# 05_Codec.net
KiCad netlist of a schematic drawn in Altium Designer
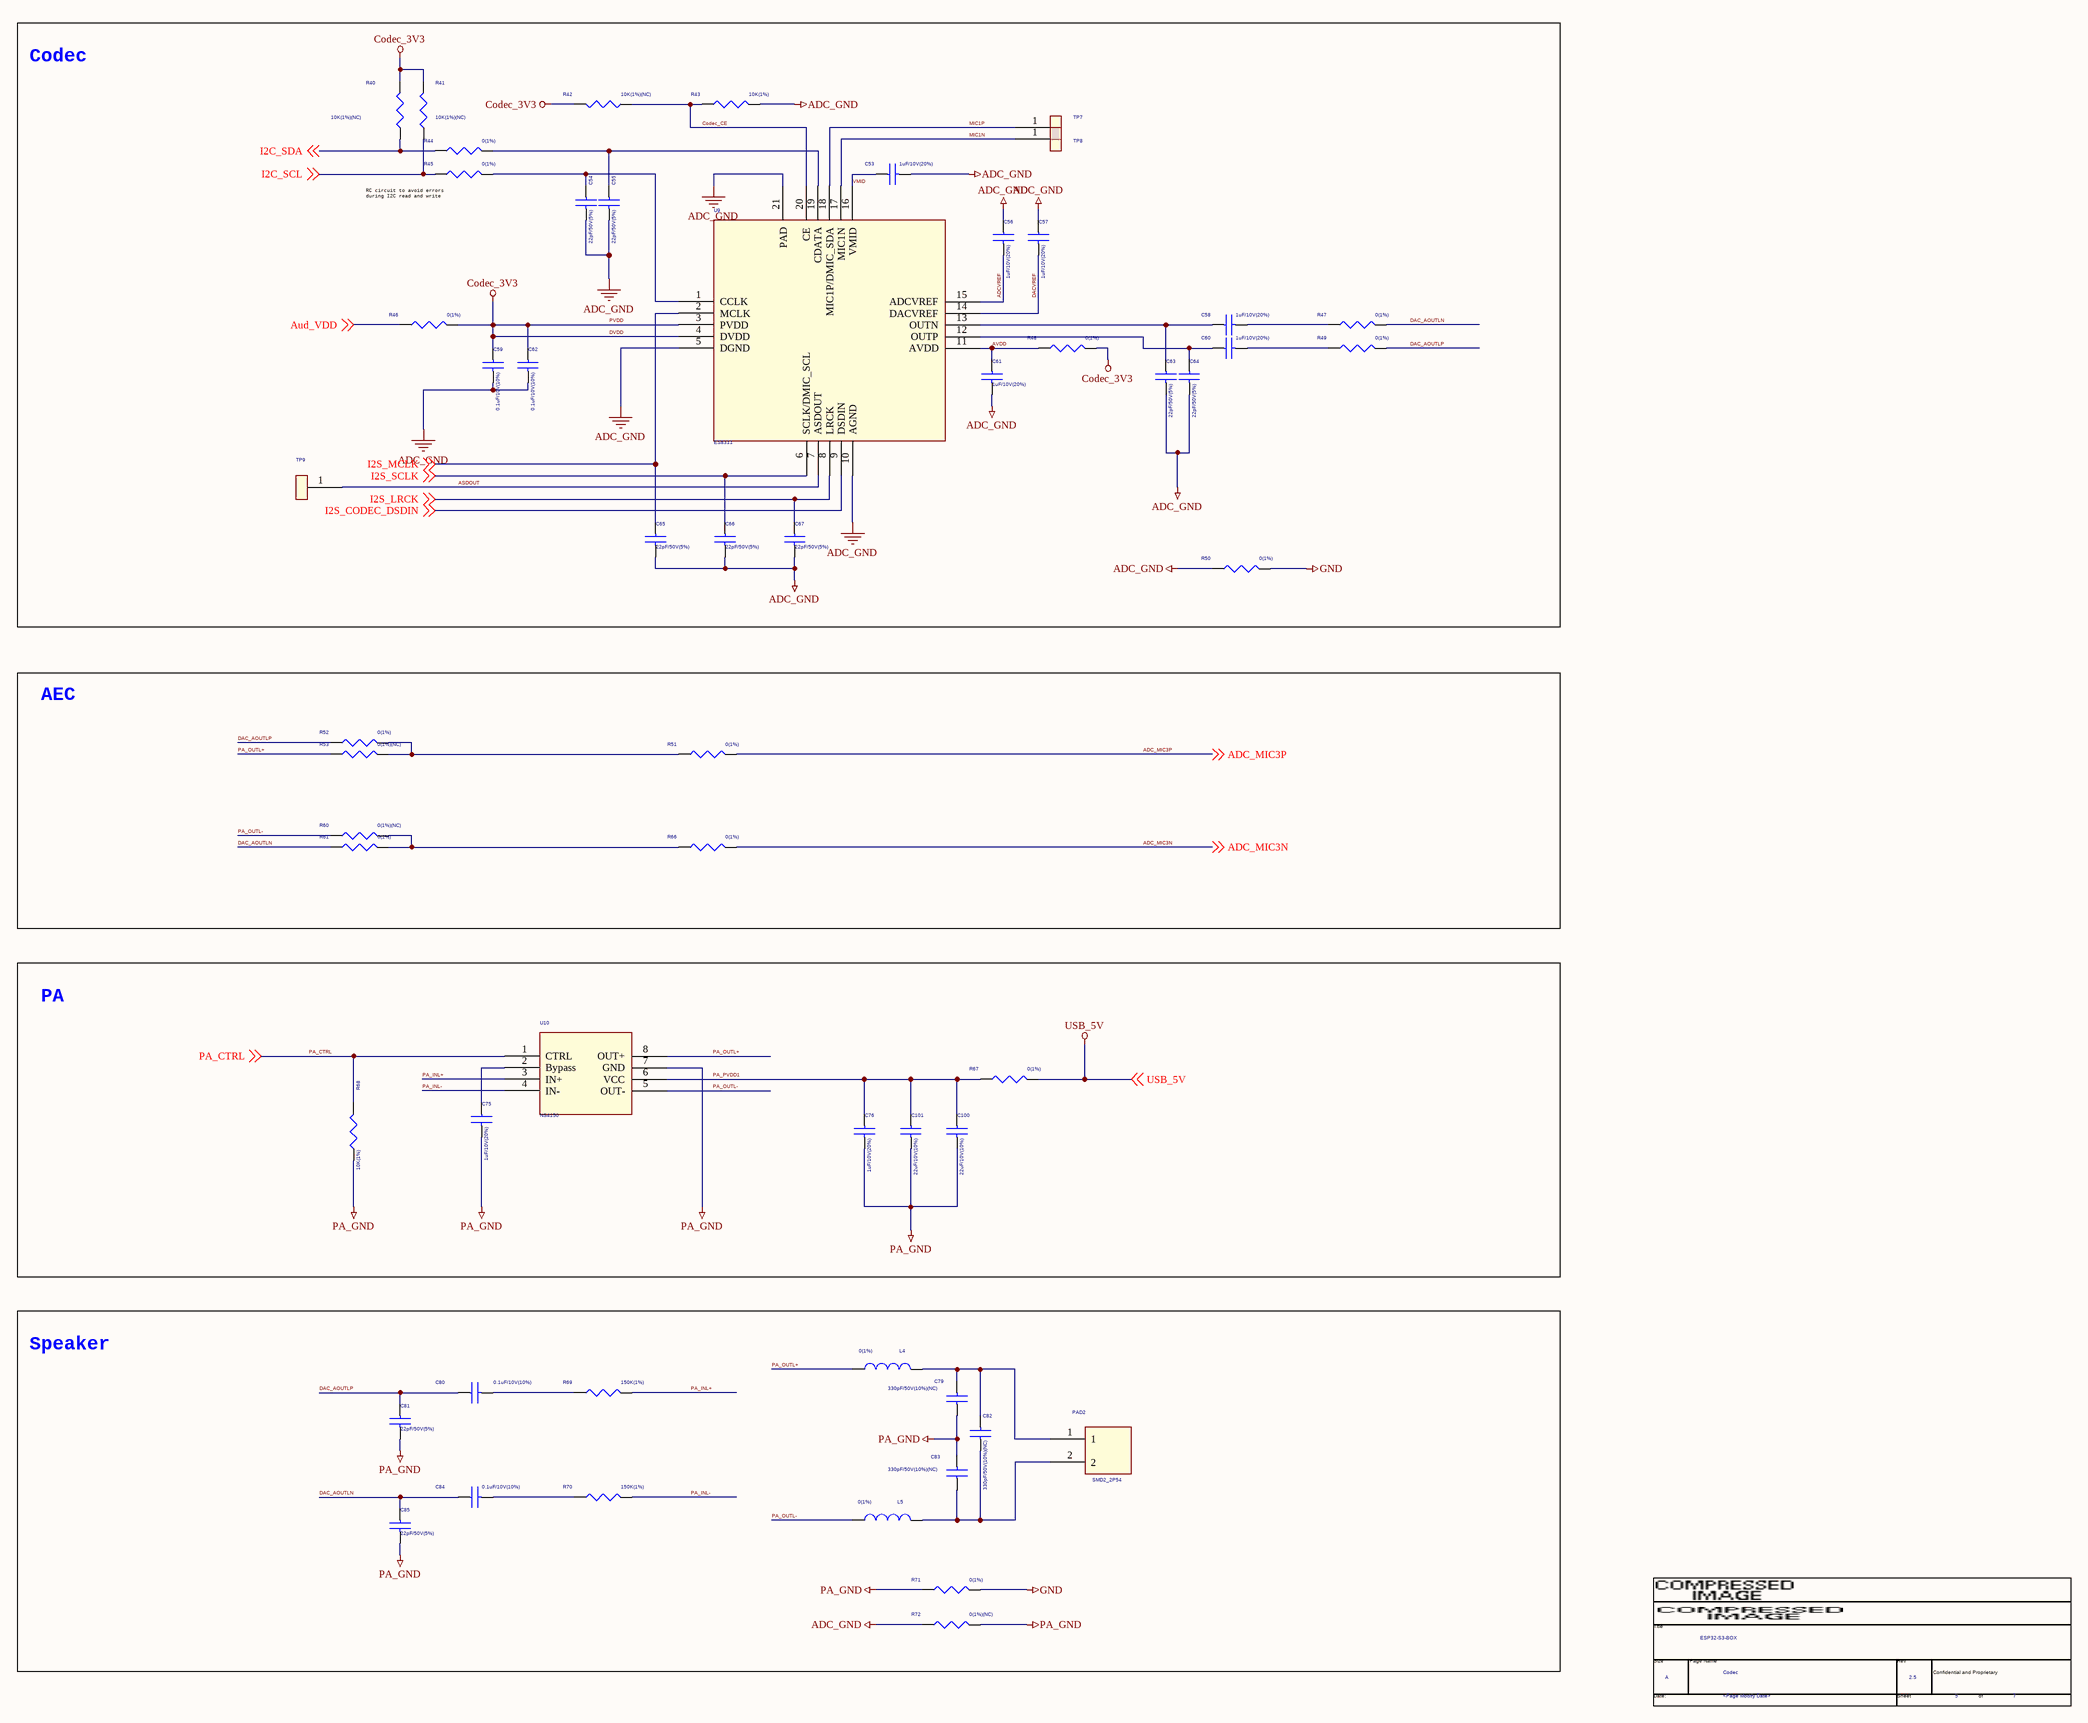
[diagram p0: 05_Codec.SchDoc]

(export (version "E")
  (design (tool "Eeschema 10.0.6"))
  (components
    (comp (ref "C53")
      (value "1uF/10V(20%)")
      (footprint "C0201")
      (fields (field (name "PART NUMBER") "ES11026103700001"))
      (libsource (lib "*") (part "CAPACITOR"))
    )
    (comp (ref "C54")
      (value "22pF/50V(5%)")
      (footprint "C0201")
      (fields (field (name "PART NUMBER") "ES11021226520000"))
      (libsource (lib "*") (part "CAPACITOR"))
    )
    (comp (ref "C55")
      (value "22pF/50V(5%)")
      (footprint "C0201")
      (fields (field (name "PART NUMBER") "ES11021226520000"))
      (libsource (lib "*") (part "CAPACITOR"))
    )
    (comp (ref "C56")
      (value "1uF/10V(20%)")
      (footprint "C0201")
      (fields (field (name "PART NUMBER") "ES11026103700001"))
      (libsource (lib "*") (part "CAPACITOR"))
    )
    (comp (ref "C57")
      (value "1uF/10V(20%)")
      (footprint "C0201")
      (fields (field (name "PART NUMBER") "ES11026103700001"))
      (libsource (lib "*") (part "CAPACITOR"))
    )
    (comp (ref "C58")
      (value "1uF/10V(20%)")
      (footprint "C0201")
      (fields (field (name "PART NUMBER") "ES11026103700001"))
      (libsource (lib "*") (part "CAPACITOR"))
    )
    (comp (ref "C59")
      (value "0.1uF/10V(10%)")
      (footprint "C0201")
      (fields (field (name "PART NUMBER") "ES11025103610001"))
      (libsource (lib "*") (part "CAPACITOR"))
    )
    (comp (ref "C60")
      (value "1uF/10V(20%)")
      (footprint "C0201")
      (fields (field (name "PART NUMBER") "ES11026103700001"))
      (libsource (lib "*") (part "CAPACITOR"))
    )
    (comp (ref "C61")
      (value "1uF/10V(20%)")
      (footprint "C0201")
      (fields (field (name "PART NUMBER") "ES11026103700001"))
      (libsource (lib "*") (part "CAPACITOR"))
    )
    (comp (ref "C62")
      (value "0.1uF/10V(10%)")
      (footprint "C0201")
      (fields (field (name "PART NUMBER") "ES11025103610001"))
      (libsource (lib "*") (part "CAPACITOR"))
    )
    (comp (ref "C63")
      (value "22pF/50V(5%)")
      (footprint "C0201")
      (fields (field (name "PART NUMBER") "ES11021226520000"))
      (libsource (lib "*") (part "CAPACITOR"))
    )
    (comp (ref "C64")
      (value "22pF/50V(5%)")
      (footprint "C0201")
      (fields (field (name "PART NUMBER") "ES11021226520000"))
      (libsource (lib "*") (part "CAPACITOR"))
    )
    (comp (ref "C65")
      (value "22pF/50V(5%)")
      (footprint "C0201")
      (fields (field (name "PART NUMBER") "ES11021226520000"))
      (libsource (lib "*") (part "CAPACITOR"))
    )
    (comp (ref "C66")
      (value "22pF/50V(5%)")
      (footprint "C0201")
      (fields (field (name "PART NUMBER") "ES11021226520000"))
      (libsource (lib "*") (part "CAPACITOR"))
    )
    (comp (ref "C67")
      (value "22pF/50V(5%)")
      (footprint "C0201")
      (fields (field (name "PART NUMBER") "ES11021226520000"))
      (libsource (lib "*") (part "CAPACITOR"))
    )
    (comp (ref "C75")
      (value "1uF/10V(20%)")
      (footprint "C0201")
      (fields (field (name "PART NUMBER") "ES11026103700001"))
      (libsource (lib "*") (part "CAPACITOR"))
    )
    (comp (ref "C76")
      (value "1uF/10V(20%)")
      (footprint "C0201")
      (fields (field (name "PART NUMBER") "ES11026103700001"))
      (libsource (lib "*") (part "CAPACITOR"))
    )
    (comp (ref "C79") (value "330pF/50V(10%)(NC)") (footprint "C0201") (libsource (lib "*") (part "CAP NP")))
    (comp (ref "C80")
      (value "0.1uF/10V(10%)")
      (footprint "C0201")
      (fields (field (name "PART NUMBER") "ES11025103610001"))
      (libsource (lib "*") (part "CAPACITOR"))
    )
    (comp (ref "C81")
      (value "22pF/50V(5%)")
      (footprint "C0201")
      (fields (field (name "PART NUMBER") "ES11021226520000"))
      (libsource (lib "*") (part "CAPACITOR"))
    )
    (comp (ref "C82") (value "330pF/50V(10%)(NC)") (footprint "C0201") (libsource (lib "*") (part "CAP NP")))
    (comp (ref "C83") (value "330pF/50V(10%)(NC)") (footprint "C0201") (libsource (lib "*") (part "CAP NP")))
    (comp (ref "C84")
      (value "0.1uF/10V(10%)")
      (footprint "C0201")
      (fields (field (name "PART NUMBER") "ES11025103610001"))
      (libsource (lib "*") (part "CAPACITOR"))
    )
    (comp (ref "C85")
      (value "22pF/50V(5%)")
      (footprint "C0201")
      (fields (field (name "PART NUMBER") "ES11021226520000"))
      (libsource (lib "*") (part "CAPACITOR"))
    )
    (comp (ref "C100")
      (value "22uF/10V(10%)")
      (footprint "C0805")
      (fields (field (name "PART NUMBER") "ES11087223720000"))
      (libsource (lib "*") (part "CAPACITOR"))
    )
    (comp (ref "C101")
      (value "22uF/10V(10%)")
      (footprint "C0805")
      (fields (field (name "PART NUMBER") "ES11087223720000"))
      (libsource (lib "*") (part "CAPACITOR"))
    )
    (comp (ref "L4") (value "0(1%)") (footprint "R0603") (libsource (lib "*") (part "INDUCTOR")))
    (comp (ref "L5") (value "0(1%)") (footprint "R0603") (libsource (lib "*") (part "INDUCTOR")))
    (comp (ref "PAD2") (value "SMD2_2P54") (footprint "SMD2_2P54") (libsource (lib "*") (part "SMD2_2P54")))
    (comp (ref "R40")
      (value "10K(1%)(NC)")
      (footprint "R0201")
      (fields (field (name "PART NUMBER") "ES21024100000001"))
      (libsource (lib "*") (part "RESISTOR"))
    )
    (comp (ref "R41")
      (value "10K(1%)(NC)")
      (footprint "R0201")
      (fields (field (name "PART NUMBER") "ES21024100000001"))
      (libsource (lib "*") (part "RESISTOR"))
    )
    (comp (ref "R42")
      (value "10K(1%)(NC)")
      (footprint "R0201")
      (fields (field (name "PART NUMBER") "ES21024100000001"))
      (libsource (lib "*") (part "RESISTOR"))
    )
    (comp (ref "R43")
      (value "10K(1%)")
      (footprint "R0201")
      (fields (field (name "PART NUMBER") "ES21024100000001"))
      (libsource (lib "*") (part "RESISTOR"))
    )
    (comp (ref "R44")
      (value "0(1%)")
      (footprint "R0201")
      (fields (field (name "PART NUMBER") "ES21020000000001"))
      (libsource (lib "*") (part "RESISTOR"))
    )
    (comp (ref "R45")
      (value "0(1%)")
      (footprint "R0201")
      (fields (field (name "PART NUMBER") "ES21020000000001"))
      (libsource (lib "*") (part "RESISTOR"))
    )
    (comp (ref "R46")
      (value "0(1%)")
      (footprint "R0402")
      (fields (field (name "PART NUMBER") "ES21040000000001"))
      (libsource (lib "*") (part "RESISTOR"))
    )
    (comp (ref "R47")
      (value "0(1%)")
      (footprint "R0201")
      (fields (field (name "PART NUMBER") "ES21020000000001"))
      (libsource (lib "*") (part "RESISTOR"))
    )
    (comp (ref "R48")
      (value "0(1%)")
      (footprint "R0402")
      (fields (field (name "PART NUMBER") "ES21040000000001"))
      (libsource (lib "*") (part "RESISTOR"))
    )
    (comp (ref "R49")
      (value "0(1%)")
      (footprint "R0201")
      (fields (field (name "PART NUMBER") "ES21020000000001"))
      (libsource (lib "*") (part "RESISTOR"))
    )
    (comp (ref "R50")
      (value "0(1%)")
      (footprint "R0402")
      (fields (field (name "PART NUMBER") "ES21040000000001"))
      (libsource (lib "*") (part "RESISTOR"))
    )
    (comp (ref "R51")
      (value "0(1%)")
      (footprint "R0201")
      (fields (field (name "PART NUMBER") "ES21020000000001"))
      (libsource (lib "*") (part "RESISTOR"))
    )
    (comp (ref "R52")
      (value "0(1%)")
      (footprint "R0201")
      (fields (field (name "PART NUMBER") "ES21020000000001"))
      (libsource (lib "*") (part "RESISTOR"))
    )
    (comp (ref "R53")
      (value "0(1%)(NC)")
      (footprint "R0201")
      (fields (field (name "PART NUMBER") "ES21020000000001"))
      (libsource (lib "*") (part "RESISTOR"))
    )
    (comp (ref "R60")
      (value "0(1%)(NC)")
      (footprint "R0201")
      (fields (field (name "PART NUMBER") "ES21020000000001"))
      (libsource (lib "*") (part "RESISTOR"))
    )
    (comp (ref "R61")
      (value "0(1%)")
      (footprint "R0201")
      (fields (field (name "PART NUMBER") "ES21020000000001"))
      (libsource (lib "*") (part "RESISTOR"))
    )
    (comp (ref "R66")
      (value "0(1%)")
      (footprint "R0201")
      (fields (field (name "PART NUMBER") "ES21020000000001"))
      (libsource (lib "*") (part "RESISTOR"))
    )
    (comp (ref "R67")
      (value "0(1%)")
      (footprint "R0402")
      (fields (field (name "PART NUMBER") "ES21040000000001"))
      (libsource (lib "*") (part "RESISTOR"))
    )
    (comp (ref "R68")
      (value "10K(1%)")
      (footprint "R0201")
      (fields (field (name "PART NUMBER") "ES21024100000001"))
      (libsource (lib "*") (part "RESISTOR"))
    )
    (comp (ref "R69")
      (value "150K(1%)")
      (footprint "R0402")
      (fields (field (name "PART NUMBER") "ES21045150000001"))
      (libsource (lib "*") (part "RESISTOR"))
    )
    (comp (ref "R70")
      (value "150K(1%)")
      (footprint "R0402")
      (fields (field (name "PART NUMBER") "ES21045150000001"))
      (libsource (lib "*") (part "RESISTOR"))
    )
    (comp (ref "R71")
      (value "0(1%)")
      (footprint "R0402")
      (fields (field (name "PART NUMBER") "ES21040000000001"))
      (libsource (lib "*") (part "RESISTOR"))
    )
    (comp (ref "R72")
      (value "0(1%)(NC)")
      (footprint "R0402")
      (fields (field (name "PART NUMBER") "ES21040000000001"))
      (libsource (lib "*") (part "RESISTOR"))
    )
    (comp (ref "TP7")
      (value "TESTPOINT")
      (footprint "TPC_D40")
      (fields (field (name "PART NUMBER") "ES51990010000000"))
      (libsource (lib "*") (part "TESTPOINT"))
    )
    (comp (ref "TP8")
      (value "TESTPOINT")
      (footprint "TPC_D40")
      (fields (field (name "PART NUMBER") "ES51990010000000"))
      (libsource (lib "*") (part "TESTPOINT"))
    )
    (comp (ref "TP9")
      (value "TESTPOINT")
      (footprint "TPC_D40")
      (fields (field (name "PART NUMBER") "ES51990010000000"))
      (libsource (lib "") (part "TESTPOINT_1"))
    )
    (comp (ref "U9")
      (value "ES8311")
      (footprint "QFN20_0P4_3")
      (fields (field (name "PART NUMBER") "ES41181204000000"))
      (libsource (lib "*") (part "ES8311"))
    )
    (comp (ref "U10")
      (value "NS4150")
      (footprint "SSOP8_0P65_5")
      (fields (field (name "PART NUMBER") "ES41180401000000"))
      (libsource (lib "*") (part "NS4150"))
    )
  )
  (nets
    (net (code "1") (name "/ADCVREF") (class "Default")
      (node (ref "C56") (pin "2") (pinfunction "2_2") (pintype "passive"))
      (node (ref "U9") (pin "15") (pinfunction "ADCVREF_15") (pintype "passive"))
    )
    (net (code "2") (name "/ASDOUT") (class "Default")
      (node (ref "TP9") (pin "1") (pinfunction "1_1") (pintype "passive"))
      (node (ref "U9") (pin "7") (pinfunction "ASDOUT_7") (pintype "passive"))
    )
    (net (code "3") (name "/AVDD") (class "Default")
      (node (ref "C61") (pin "1") (pinfunction "1_1") (pintype "passive"))
      (node (ref "R48") (pin "1") (pinfunction "1_1") (pintype "passive"))
      (node (ref "U9") (pin "11") (pinfunction "AVDD_11") (pintype "passive"))
    )
    (net (code "4") (name "/Codec_CE") (class "Default")
      (node (ref "R42") (pin "1") (pinfunction "1_1") (pintype "passive"))
      (node (ref "R43") (pin "1") (pinfunction "1_1") (pintype "passive"))
      (node (ref "U9") (pin "20") (pinfunction "CE_20") (pintype "passive"))
    )
    (net (code "5") (name "/DACVREF") (class "Default")
      (node (ref "C57") (pin "2") (pinfunction "2_2") (pintype "passive"))
      (node (ref "U9") (pin "14") (pinfunction "DACVREF_14") (pintype "passive"))
    )
    (net (code "6") (name "/DAC_AOUTLN") (class "Default")
      (node (ref "C84") (pin "1") (pinfunction "1_1") (pintype "passive"))
      (node (ref "C85") (pin "1") (pinfunction "1_1") (pintype "passive"))
      (node (ref "R47") (pin "2") (pinfunction "2_2") (pintype "passive"))
      (node (ref "R61") (pin "1") (pinfunction "1_1") (pintype "passive"))
    )
    (net (code "7") (name "/DAC_AOUTLP") (class "Default")
      (node (ref "C80") (pin "1") (pinfunction "1_1") (pintype "passive"))
      (node (ref "C81") (pin "1") (pinfunction "1_1") (pintype "passive"))
      (node (ref "R49") (pin "2") (pinfunction "2_2") (pintype "passive"))
      (node (ref "R52") (pin "1") (pinfunction "1_1") (pintype "passive"))
    )
    (net (code "8") (name "/MIC1N") (class "Default")
      (node (ref "TP8") (pin "1") (pinfunction "1_1") (pintype "passive"))
      (node (ref "U9") (pin "17") (pinfunction "MIC1N_17") (pintype "passive"))
    )
    (net (code "9") (name "/MIC1P") (class "Default")
      (node (ref "TP7") (pin "1") (pinfunction "1_1") (pintype "passive"))
      (node (ref "U9") (pin "18") (pinfunction "MIC1P/DMIC_SDA_18") (pintype "passive"))
    )
    (net (code "10") (name "/PA_INL+") (class "Default")
      (node (ref "R69") (pin "2") (pinfunction "2_2") (pintype "passive"))
      (node (ref "U10") (pin "3") (pinfunction "IN+_3") (pintype "passive"))
    )
    (net (code "11") (name "/PA_INL-") (class "Default")
      (node (ref "R70") (pin "2") (pinfunction "2_2") (pintype "passive"))
      (node (ref "U10") (pin "4") (pinfunction "IN-_4") (pintype "passive"))
    )
    (net (code "12") (name "/PA_OUTL+") (class "Default")
      (node (ref "L4") (pin "2") (pinfunction "2_2") (pintype "passive"))
      (node (ref "R53") (pin "1") (pinfunction "1_1") (pintype "passive"))
      (node (ref "U10") (pin "8") (pinfunction "OUT+_8") (pintype "passive"))
    )
    (net (code "13") (name "/PA_OUTL-") (class "Default")
      (node (ref "L5") (pin "2") (pinfunction "2_2") (pintype "passive"))
      (node (ref "R60") (pin "1") (pinfunction "1_1") (pintype "passive"))
      (node (ref "U10") (pin "5") (pinfunction "OUT-_5") (pintype "passive"))
    )
    (net (code "14") (name "/PA_PVDD1") (class "Default")
      (node (ref "C100") (pin "1") (pinfunction "1_1") (pintype "passive"))
      (node (ref "C101") (pin "1") (pinfunction "1_1") (pintype "passive"))
      (node (ref "C76") (pin "1") (pinfunction "1_1") (pintype "passive"))
      (node (ref "R67") (pin "1") (pinfunction "1_1") (pintype "passive"))
      (node (ref "U10") (pin "6") (pinfunction "VCC_6") (pintype "passive"))
    )
    (net (code "15") (name "/VMID") (class "Default")
      (node (ref "C53") (pin "1") (pinfunction "1_1") (pintype "passive"))
      (node (ref "U9") (pin "16") (pinfunction "VMID_16") (pintype "passive"))
    )
    (net (code "16") (name "ADC_GND") (class "Default")
      (node (ref "C53") (pin "2") (pinfunction "2_2") (pintype "passive"))
      (node (ref "C54") (pin "2") (pinfunction "2_2") (pintype "passive"))
      (node (ref "C55") (pin "2") (pinfunction "2_2") (pintype "passive"))
      (node (ref "C56") (pin "1") (pinfunction "1_1") (pintype "passive"))
      (node (ref "C57") (pin "1") (pinfunction "1_1") (pintype "passive"))
      (node (ref "C59") (pin "2") (pinfunction "2_2") (pintype "passive"))
      (node (ref "C61") (pin "2") (pinfunction "2_2") (pintype "passive"))
      (node (ref "C62") (pin "2") (pinfunction "2_2") (pintype "passive"))
      (node (ref "C63") (pin "2") (pinfunction "2_2") (pintype "passive"))
      (node (ref "C64") (pin "2") (pinfunction "2_2") (pintype "passive"))
      (node (ref "C65") (pin "2") (pinfunction "2_2") (pintype "passive"))
      (node (ref "C66") (pin "2") (pinfunction "2_2") (pintype "passive"))
      (node (ref "C67") (pin "2") (pinfunction "2_2") (pintype "passive"))
      (node (ref "R43") (pin "2") (pinfunction "2_2") (pintype "passive"))
      (node (ref "R50") (pin "1") (pinfunction "1_1") (pintype "passive"))
      (node (ref "R72") (pin "1") (pinfunction "1_1") (pintype "passive"))
      (node (ref "U9") (pin "10") (pinfunction "AGND_10") (pintype "passive"))
      (node (ref "U9") (pin "21") (pinfunction "PAD_21") (pintype "passive"))
      (node (ref "U9") (pin "5") (pinfunction "DGND_5") (pintype "passive"))
    )
    (net (code "17") (name "ADC_MIC3N") (class "Default")
      (node (ref "R66") (pin "2") (pinfunction "2_2") (pintype "passive"))
    )
    (net (code "18") (name "ADC_MIC3P") (class "Default")
      (node (ref "R51") (pin "2") (pinfunction "2_2") (pintype "passive"))
    )
    (net (code "19") (name "Aud_VDD") (class "Default")
      (node (ref "R46") (pin "1") (pinfunction "1_1") (pintype "passive"))
    )
    (net (code "20") (name "Codec_3V3") (class "Default")
      (node (ref "C59") (pin "1") (pinfunction "1_1") (pintype "passive"))
      (node (ref "C62") (pin "1") (pinfunction "1_1") (pintype "passive"))
      (node (ref "R40") (pin "2") (pinfunction "2_2") (pintype "passive"))
      (node (ref "R41") (pin "2") (pinfunction "2_2") (pintype "passive"))
      (node (ref "R42") (pin "2") (pinfunction "2_2") (pintype "passive"))
      (node (ref "R46") (pin "2") (pinfunction "2_2") (pintype "passive"))
      (node (ref "R48") (pin "2") (pinfunction "2_2") (pintype "passive"))
      (node (ref "U9") (pin "3") (pinfunction "PVDD_3") (pintype "passive"))
      (node (ref "U9") (pin "4") (pinfunction "DVDD_4") (pintype "passive"))
    )
    (net (code "21") (name "GND") (class "Default")
      (node (ref "R50") (pin "2") (pinfunction "2_2") (pintype "passive"))
      (node (ref "R71") (pin "2") (pinfunction "2_2") (pintype "passive"))
    )
    (net (code "22") (name "I2C_SCL") (class "Default")
      (node (ref "R41") (pin "1") (pinfunction "1_1") (pintype "passive"))
      (node (ref "R45") (pin "1") (pinfunction "1_1") (pintype "passive"))
    )
    (net (code "23") (name "I2C_SDA") (class "Default")
      (node (ref "R40") (pin "1") (pinfunction "1_1") (pintype "passive"))
      (node (ref "R44") (pin "1") (pinfunction "1_1") (pintype "passive"))
    )
    (net (code "24") (name "I2S_CODEC_DSDIN") (class "Default")
      (node (ref "U9") (pin "9") (pinfunction "DSDIN_9") (pintype "passive"))
    )
    (net (code "25") (name "I2S_LRCK") (class "Default")
      (node (ref "C67") (pin "1") (pinfunction "1_1") (pintype "passive"))
      (node (ref "U9") (pin "8") (pinfunction "LRCK_8") (pintype "passive"))
    )
    (net (code "26") (name "I2S_MCLK") (class "Default")
      (node (ref "C65") (pin "1") (pinfunction "1_1") (pintype "passive"))
      (node (ref "U9") (pin "2") (pinfunction "MCLK_2") (pintype "passive"))
    )
    (net (code "27") (name "I2S_SCLK") (class "Default")
      (node (ref "C66") (pin "1") (pinfunction "1_1") (pintype "passive"))
      (node (ref "U9") (pin "6") (pinfunction "SCLK/DMIC_SCL_6") (pintype "passive"))
    )
    (net (code "28") (name "Net-(C58-Pad2)") (class "Default")
      (node (ref "C58") (pin "2") (pinfunction "2_2") (pintype "passive"))
      (node (ref "R47") (pin "1") (pinfunction "1_1") (pintype "passive"))
    )
    (net (code "29") (name "Net-(C60-Pad2)") (class "Default")
      (node (ref "C60") (pin "2") (pinfunction "2_2") (pintype "passive"))
      (node (ref "R49") (pin "1") (pinfunction "1_1") (pintype "passive"))
    )
    (net (code "30") (name "Net-(C79-Pad2)") (class "Default")
      (node (ref "C79") (pin "2") (pinfunction "2_2") (pintype "passive"))
      (node (ref "C82") (pin "2") (pinfunction "2_2") (pintype "passive"))
      (node (ref "L4") (pin "1") (pinfunction "1_1") (pintype "passive"))
      (node (ref "PAD2") (pin "1") (pinfunction "1_1") (pintype "passive"))
    )
    (net (code "31") (name "Net-(C80-Pad2)") (class "Default")
      (node (ref "C80") (pin "2") (pinfunction "2_2") (pintype "passive"))
      (node (ref "R69") (pin "1") (pinfunction "1_1") (pintype "passive"))
    )
    (net (code "32") (name "Net-(C82-Pad1)") (class "Default")
      (node (ref "C82") (pin "1") (pinfunction "1_1") (pintype "passive"))
      (node (ref "C83") (pin "1") (pinfunction "1_1") (pintype "passive"))
      (node (ref "L5") (pin "1") (pinfunction "1_1") (pintype "passive"))
      (node (ref "PAD2") (pin "2") (pinfunction "2_2") (pintype "passive"))
    )
    (net (code "33") (name "Net-(C84-Pad2)") (class "Default")
      (node (ref "C84") (pin "2") (pinfunction "2_2") (pintype "passive"))
      (node (ref "R70") (pin "1") (pinfunction "1_1") (pintype "passive"))
    )
    (net (code "34") (name "Net-(R51-Pad1)") (class "Default")
      (node (ref "R51") (pin "1") (pinfunction "1_1") (pintype "passive"))
      (node (ref "R52") (pin "2") (pinfunction "2_2") (pintype "passive"))
      (node (ref "R53") (pin "2") (pinfunction "2_2") (pintype "passive"))
    )
    (net (code "35") (name "Net-(R60-Pad2)") (class "Default")
      (node (ref "R60") (pin "2") (pinfunction "2_2") (pintype "passive"))
      (node (ref "R61") (pin "2") (pinfunction "2_2") (pintype "passive"))
      (node (ref "R66") (pin "1") (pinfunction "1_1") (pintype "passive"))
    )
    (net (code "36") (name "Net-(U9-CCLK)") (class "Default")
      (node (ref "C54") (pin "1") (pinfunction "1_1") (pintype "passive"))
      (node (ref "R45") (pin "2") (pinfunction "2_2") (pintype "passive"))
      (node (ref "U9") (pin "1") (pinfunction "CCLK_1") (pintype "passive"))
    )
    (net (code "37") (name "Net-(U9-CDATA)") (class "Default")
      (node (ref "C55") (pin "1") (pinfunction "1_1") (pintype "passive"))
      (node (ref "R44") (pin "2") (pinfunction "2_2") (pintype "passive"))
      (node (ref "U9") (pin "19") (pinfunction "CDATA_19") (pintype "passive"))
    )
    (net (code "38") (name "Net-(U9-OUTN)") (class "Default")
      (node (ref "C58") (pin "1") (pinfunction "1_1") (pintype "passive"))
      (node (ref "C63") (pin "1") (pinfunction "1_1") (pintype "passive"))
      (node (ref "U9") (pin "13") (pinfunction "OUTN_13") (pintype "passive"))
    )
    (net (code "39") (name "Net-(U9-OUTP)") (class "Default")
      (node (ref "C60") (pin "1") (pinfunction "1_1") (pintype "passive"))
      (node (ref "C64") (pin "1") (pinfunction "1_1") (pintype "passive"))
      (node (ref "U9") (pin "12") (pinfunction "OUTP_12") (pintype "passive"))
    )
    (net (code "40") (name "Net-(U10-Bypass)") (class "Default")
      (node (ref "C75") (pin "1") (pinfunction "1_1") (pintype "passive"))
      (node (ref "U10") (pin "2") (pinfunction "Bypass_2") (pintype "passive"))
    )
    (net (code "41") (name "PA_CTRL") (class "Default")
      (node (ref "R68") (pin "2") (pinfunction "2_2") (pintype "passive"))
      (node (ref "U10") (pin "1") (pinfunction "CTRL_1") (pintype "passive"))
    )
    (net (code "42") (name "PA_GND") (class "Default")
      (node (ref "C100") (pin "2") (pinfunction "2_2") (pintype "passive"))
      (node (ref "C101") (pin "2") (pinfunction "2_2") (pintype "passive"))
      (node (ref "C75") (pin "2") (pinfunction "2_2") (pintype "passive"))
      (node (ref "C76") (pin "2") (pinfunction "2_2") (pintype "passive"))
      (node (ref "C79") (pin "1") (pinfunction "1_1") (pintype "passive"))
      (node (ref "C81") (pin "2") (pinfunction "2_2") (pintype "passive"))
      (node (ref "C83") (pin "2") (pinfunction "2_2") (pintype "passive"))
      (node (ref "C85") (pin "2") (pinfunction "2_2") (pintype "passive"))
      (node (ref "R68") (pin "1") (pinfunction "1_1") (pintype "passive"))
      (node (ref "R71") (pin "1") (pinfunction "1_1") (pintype "passive"))
      (node (ref "R72") (pin "2") (pinfunction "2_2") (pintype "passive"))
      (node (ref "U10") (pin "7") (pinfunction "GND_7") (pintype "passive"))
    )
    (net (code "43") (name "USB_5V") (class "Default")
      (node (ref "R67") (pin "2") (pinfunction "2_2") (pintype "passive"))
    )
  )
)
